# pwm_outputs.net
KiCad netlist of a schematic drawn in Altium Designer
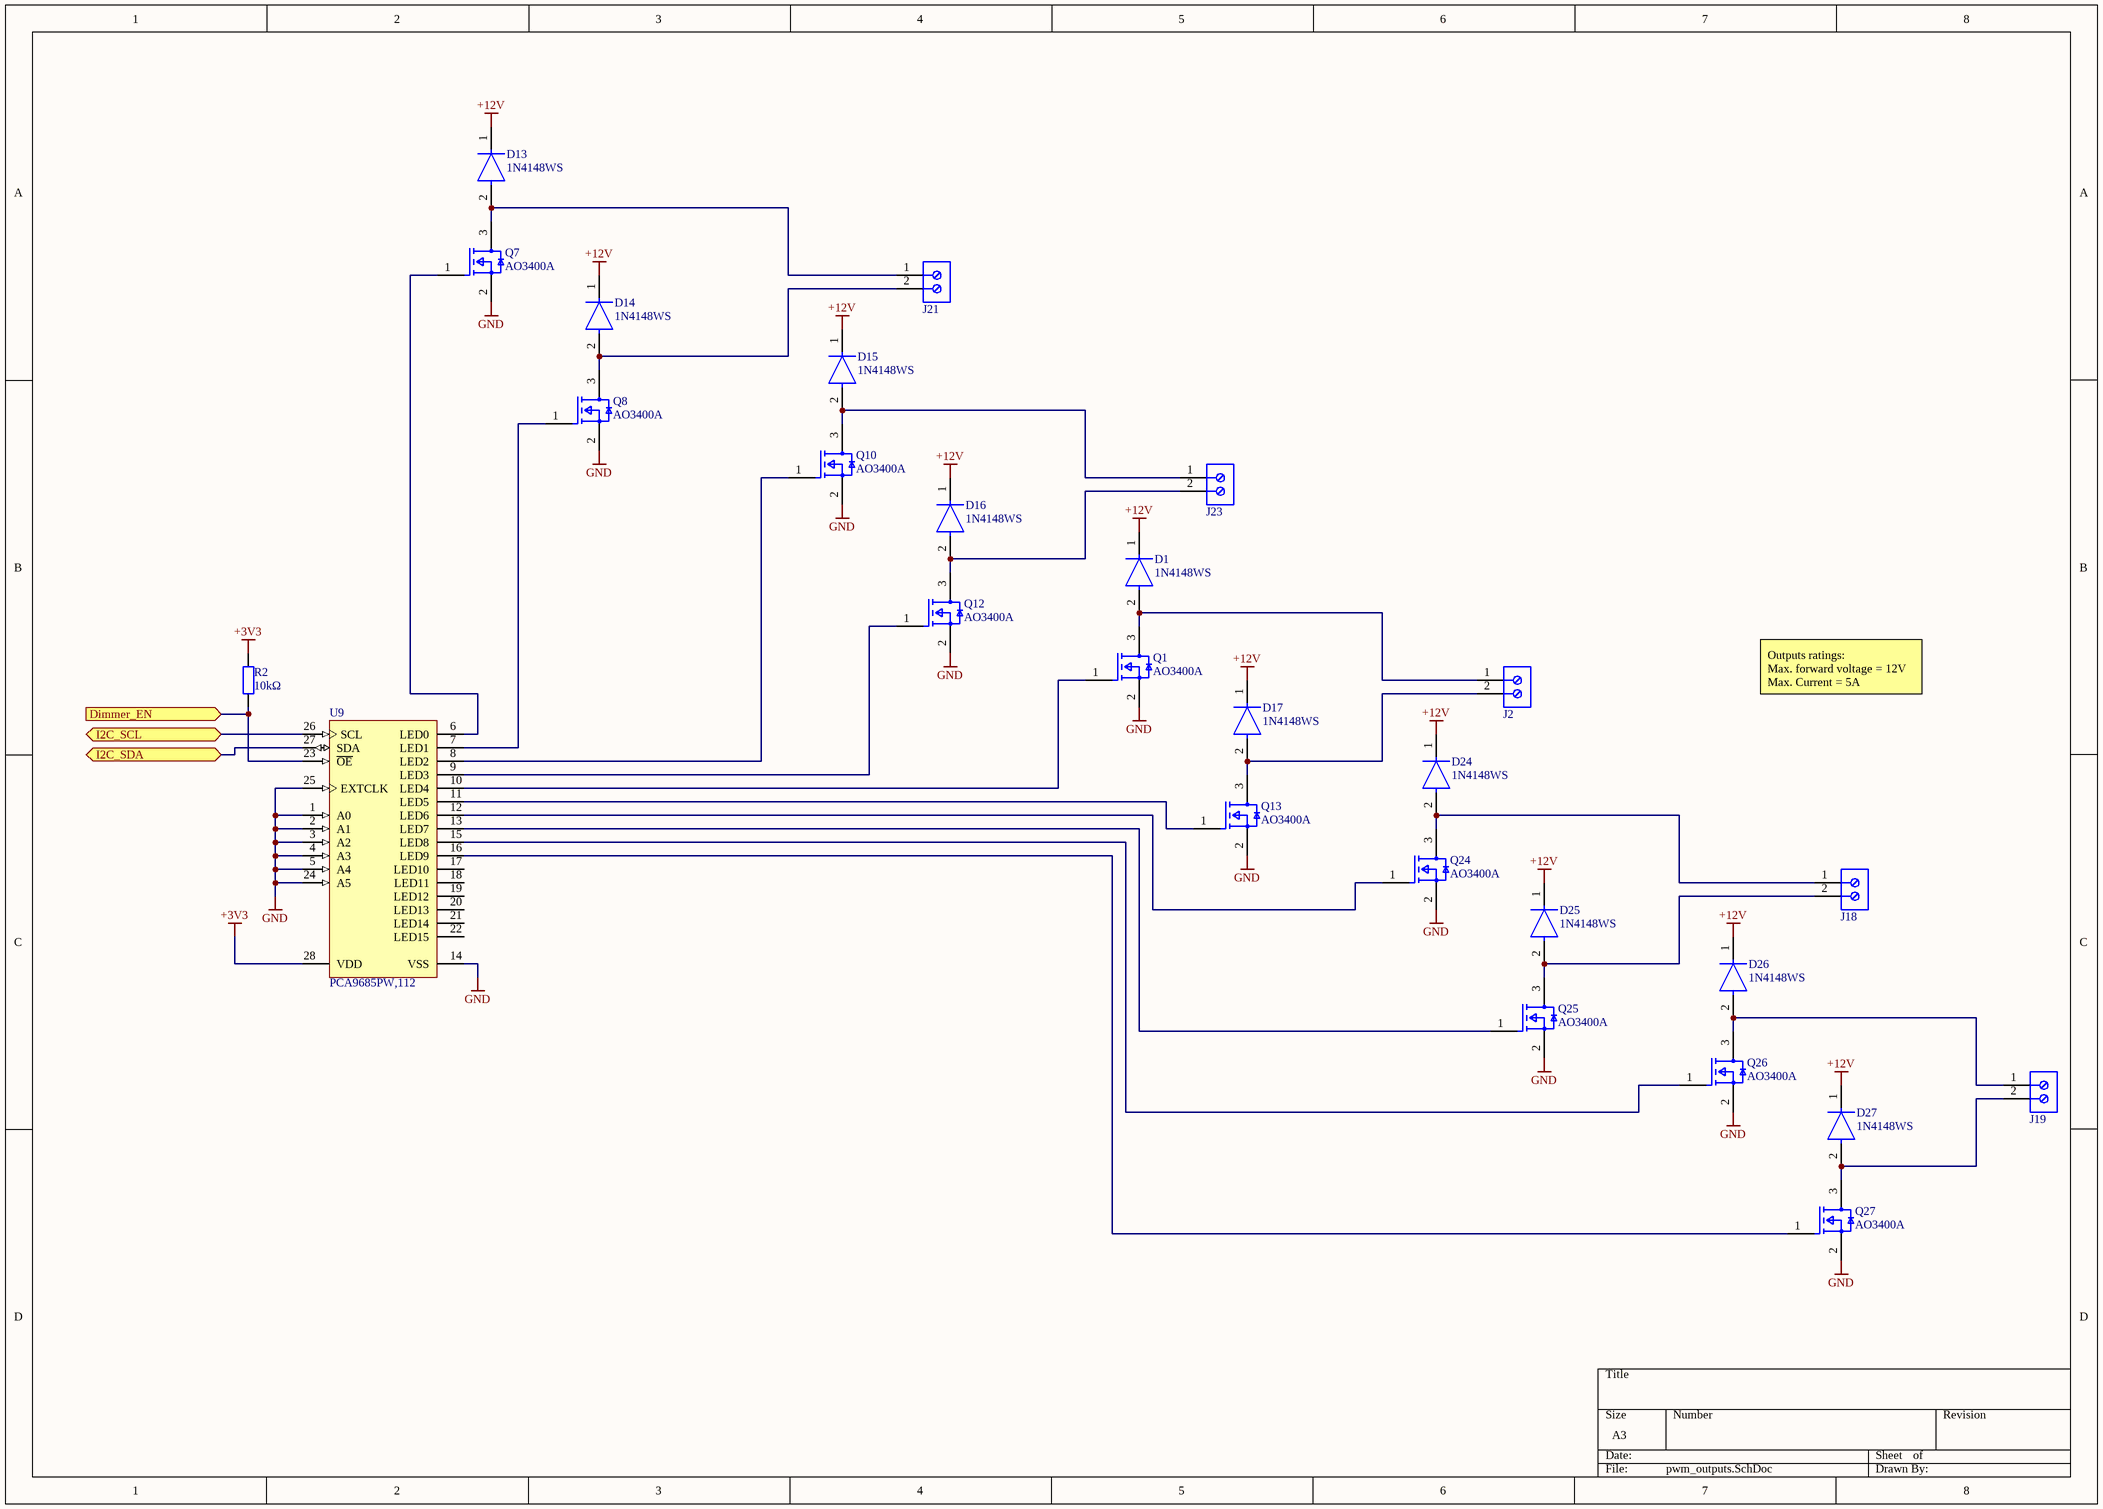
[diagram p0: pwm_outputs.SchDoc]

(export (version "E")
  (design (tool "Eeschema 10.0.6"))
  (components
    (comp (ref "D1")
      (value "1N4148WS")
      (footprint "FP-477AB-IPC_C")
      (description "DIODE GEN PURP 75V 150MA SOD323F")
      (libsource (lib "Altium Content Vault") (part "d7152d700b627762746794eb795d46e"))
    )
    (comp (ref "D13")
      (value "1N4148WS")
      (footprint "FP-477AB-IPC_C")
      (description "DIODE GEN PURP 75V 150MA SOD323F")
      (libsource (lib "Altium Content Vault") (part "d7152d700b627762746794eb795d46e"))
    )
    (comp (ref "D14")
      (value "1N4148WS")
      (footprint "FP-477AB-IPC_C")
      (description "DIODE GEN PURP 75V 150MA SOD323F")
      (libsource (lib "Altium Content Vault") (part "d7152d700b627762746794eb795d46e"))
    )
    (comp (ref "D15")
      (value "1N4148WS")
      (footprint "FP-477AB-IPC_C")
      (description "DIODE GEN PURP 75V 150MA SOD323F")
      (libsource (lib "Altium Content Vault") (part "d7152d700b627762746794eb795d46e"))
    )
    (comp (ref "D16")
      (value "1N4148WS")
      (footprint "FP-477AB-IPC_C")
      (description "DIODE GEN PURP 75V 150MA SOD323F")
      (libsource (lib "Altium Content Vault") (part "d7152d700b627762746794eb795d46e"))
    )
    (comp (ref "D17")
      (value "1N4148WS")
      (footprint "FP-477AB-IPC_C")
      (description "DIODE GEN PURP 75V 150MA SOD323F")
      (libsource (lib "Altium Content Vault") (part "d7152d700b627762746794eb795d46e"))
    )
    (comp (ref "D24")
      (value "1N4148WS")
      (footprint "FP-477AB-IPC_C")
      (description "DIODE GEN PURP 75V 150MA SOD323F")
      (libsource (lib "Altium Content Vault") (part "d7152d700b627762746794eb795d46e"))
    )
    (comp (ref "D25")
      (value "1N4148WS")
      (footprint "FP-477AB-IPC_C")
      (description "DIODE GEN PURP 75V 150MA SOD323F")
      (libsource (lib "Altium Content Vault") (part "d7152d700b627762746794eb795d46e"))
    )
    (comp (ref "D26")
      (value "1N4148WS")
      (footprint "FP-477AB-IPC_C")
      (description "DIODE GEN PURP 75V 150MA SOD323F")
      (libsource (lib "Altium Content Vault") (part "d7152d700b627762746794eb795d46e"))
    )
    (comp (ref "D27")
      (value "1N4148WS")
      (footprint "FP-477AB-IPC_C")
      (description "DIODE GEN PURP 75V 150MA SOD323F")
      (libsource (lib "Altium Content Vault") (part "d7152d700b627762746794eb795d46e"))
    )
    (comp (ref "J2")
      (value "282836-2")
      (footprint "TECO-282836-2_V")
      (description "Female Header, Pitch 5 mm, 1 x 2 Position, Height 10 mm, Tail Length 3.5 mm, Rohs, Bulk")
      (fields (field (name "VOLTAGE") "300V") (field (name "MANUFACTURER") "TE Connectivity"))
      (libsource (lib "Altium Content Vault") (part "CN-1P-F-TB2"))
    )
    (comp (ref "J18")
      (value "282836-2")
      (footprint "TECO-282836-2_V")
      (description "Female Header, Pitch 5 mm, 1 x 2 Position, Height 10 mm, Tail Length 3.5 mm, Rohs, Bulk")
      (fields (field (name "VOLTAGE") "300V") (field (name "MANUFACTURER") "TE Connectivity"))
      (libsource (lib "Altium Content Vault") (part "CN-1P-F-TB2"))
    )
    (comp (ref "J19")
      (value "282836-2")
      (footprint "TECO-282836-2_V")
      (description "Female Header, Pitch 5 mm, 1 x 2 Position, Height 10 mm, Tail Length 3.5 mm, Rohs, Bulk")
      (fields (field (name "VOLTAGE") "300V") (field (name "MANUFACTURER") "TE Connectivity"))
      (libsource (lib "Altium Content Vault") (part "CN-1P-F-TB2"))
    )
    (comp (ref "J21")
      (value "282836-2")
      (footprint "TECO-282836-2_V")
      (description "Female Header, Pitch 5 mm, 1 x 2 Position, Height 10 mm, Tail Length 3.5 mm, Rohs, Bulk")
      (fields (field (name "VOLTAGE") "300V") (field (name "MANUFACTURER") "TE Connectivity"))
      (libsource (lib "Altium Content Vault") (part "CN-1P-F-TB2"))
    )
    (comp (ref "J23")
      (value "282836-2")
      (footprint "TECO-282836-2_V")
      (description "Female Header, Pitch 5 mm, 1 x 2 Position, Height 10 mm, Tail Length 3.5 mm, Rohs, Bulk")
      (fields (field (name "VOLTAGE") "300V") (field (name "MANUFACTURER") "TE Connectivity"))
      (libsource (lib "Altium Content Vault") (part "CN-1P-F-TB2"))
    )
    (comp (ref "Q1")
      (value "AO3400A")
      (footprint "SOT-23")
      (description "MOSFET N-CH 30V 5.7A SOT23")
      (libsource (lib "integrated_library") (part "MOSFET_AO3400A"))
    )
    (comp (ref "Q7")
      (value "AO3400A")
      (footprint "SOT-23")
      (description "MOSFET N-CH 30V 5.7A SOT23")
      (libsource (lib "integrated_library") (part "MOSFET_AO3400A"))
    )
    (comp (ref "Q8")
      (value "AO3400A")
      (footprint "SOT-23")
      (description "MOSFET N-CH 30V 5.7A SOT23")
      (libsource (lib "integrated_library") (part "MOSFET_AO3400A"))
    )
    (comp (ref "Q10")
      (value "AO3400A")
      (footprint "SOT-23")
      (description "MOSFET N-CH 30V 5.7A SOT23")
      (libsource (lib "integrated_library") (part "MOSFET_AO3400A"))
    )
    (comp (ref "Q12")
      (value "AO3400A")
      (footprint "SOT-23")
      (description "MOSFET N-CH 30V 5.7A SOT23")
      (libsource (lib "integrated_library") (part "MOSFET_AO3400A"))
    )
    (comp (ref "Q13")
      (value "AO3400A")
      (footprint "SOT-23")
      (description "MOSFET N-CH 30V 5.7A SOT23")
      (libsource (lib "integrated_library") (part "MOSFET_AO3400A"))
    )
    (comp (ref "Q24")
      (value "AO3400A")
      (footprint "SOT-23")
      (description "MOSFET N-CH 30V 5.7A SOT23")
      (libsource (lib "integrated_library") (part "MOSFET_AO3400A"))
    )
    (comp (ref "Q25")
      (value "AO3400A")
      (footprint "SOT-23")
      (description "MOSFET N-CH 30V 5.7A SOT23")
      (libsource (lib "integrated_library") (part "MOSFET_AO3400A"))
    )
    (comp (ref "Q26")
      (value "AO3400A")
      (footprint "SOT-23")
      (description "MOSFET N-CH 30V 5.7A SOT23")
      (libsource (lib "integrated_library") (part "MOSFET_AO3400A"))
    )
    (comp (ref "Q27")
      (value "AO3400A")
      (footprint "SOT-23")
      (description "MOSFET N-CH 30V 5.7A SOT23")
      (libsource (lib "integrated_library") (part "MOSFET_AO3400A"))
    )
    (comp (ref "R2")
      (value "10kΩ")
      (footprint "RESC2013X50X30ML20T20")
      (description "Resistor")
      (libsource (lib "PCB_Project") (part "Res_0805"))
    )
    (comp (ref "U9")
      (value "PCA9685PW,112")
      (footprint "SOT361-1_V")
      (fields (field (name "PARTNUMBER") "PCA9685"))
      (libsource (lib "Altium Content Vault") (part "NXP-PCA9685-SOT361-1"))
    )
  )
  (nets
    (net (code "1") (name "+3V3") (class "Default")
      (node (ref "R2") (pin "2") (pinfunction "2_2") (pintype "passive"))
      (node (ref "U9") (pin "28") (pinfunction "VDD_28") (pintype "power_in"))
    )
    (net (code "2") (name "+12V") (class "Default")
      (node (ref "D1") (pin "1") (pinfunction "C_1") (pintype "passive"))
      (node (ref "D13") (pin "1") (pinfunction "C_1") (pintype "passive"))
      (node (ref "D14") (pin "1") (pinfunction "C_1") (pintype "passive"))
      (node (ref "D15") (pin "1") (pinfunction "C_1") (pintype "passive"))
      (node (ref "D16") (pin "1") (pinfunction "C_1") (pintype "passive"))
      (node (ref "D17") (pin "1") (pinfunction "C_1") (pintype "passive"))
      (node (ref "D24") (pin "1") (pinfunction "C_1") (pintype "passive"))
      (node (ref "D25") (pin "1") (pinfunction "C_1") (pintype "passive"))
      (node (ref "D26") (pin "1") (pinfunction "C_1") (pintype "passive"))
      (node (ref "D27") (pin "1") (pinfunction "C_1") (pintype "passive"))
    )
    (net (code "3") (name "/Dimmer_EN") (class "Default")
      (node (ref "R2") (pin "1") (pinfunction "1_1") (pintype "passive"))
      (node (ref "U9") (pin "23") (pinfunction "~{OE}_23") (pintype "input"))
    )
    (net (code "4") (name "/I2C_SCL") (class "Default")
      (node (ref "U9") (pin "26") (pinfunction "SCL_26") (pintype "input"))
    )
    (net (code "5") (name "/I2C_SDA") (class "Default")
      (node (ref "U9") (pin "27") (pinfunction "SDA_27") (pintype "bidirectional"))
    )
    (net (code "6") (name "GND") (class "Default")
      (node (ref "Q1") (pin "2") (pinfunction "S_2") (pintype "passive"))
      (node (ref "Q10") (pin "2") (pinfunction "S_2") (pintype "passive"))
      (node (ref "Q12") (pin "2") (pinfunction "S_2") (pintype "passive"))
      (node (ref "Q13") (pin "2") (pinfunction "S_2") (pintype "passive"))
      (node (ref "Q24") (pin "2") (pinfunction "S_2") (pintype "passive"))
      (node (ref "Q25") (pin "2") (pinfunction "S_2") (pintype "passive"))
      (node (ref "Q26") (pin "2") (pinfunction "S_2") (pintype "passive"))
      (node (ref "Q27") (pin "2") (pinfunction "S_2") (pintype "passive"))
      (node (ref "Q7") (pin "2") (pinfunction "S_2") (pintype "passive"))
      (node (ref "Q8") (pin "2") (pinfunction "S_2") (pintype "passive"))
      (node (ref "U9") (pin "1") (pinfunction "A0_1") (pintype "input"))
      (node (ref "U9") (pin "14") (pinfunction "VSS_14") (pintype "power_in"))
      (node (ref "U9") (pin "2") (pinfunction "A1_2") (pintype "input"))
      (node (ref "U9") (pin "24") (pinfunction "A5_24") (pintype "input"))
      (node (ref "U9") (pin "25") (pinfunction "EXTCLK_25") (pintype "input"))
      (node (ref "U9") (pin "3") (pinfunction "A2_3") (pintype "input"))
      (node (ref "U9") (pin "4") (pinfunction "A3_4") (pintype "input"))
      (node (ref "U9") (pin "5") (pinfunction "A4_5") (pintype "input"))
    )
    (net (code "7") (name "Net-(D1-A)") (class "Default")
      (node (ref "D1") (pin "2") (pinfunction "A_2") (pintype "passive"))
      (node (ref "J2") (pin "1") (pinfunction "1_1") (pintype "passive"))
      (node (ref "Q1") (pin "3") (pinfunction "D_3") (pintype "passive"))
    )
    (net (code "8") (name "Net-(D13-A)") (class "Default")
      (node (ref "D13") (pin "2") (pinfunction "A_2") (pintype "passive"))
      (node (ref "J21") (pin "1") (pinfunction "1_1") (pintype "passive"))
      (node (ref "Q7") (pin "3") (pinfunction "D_3") (pintype "passive"))
    )
    (net (code "9") (name "Net-(D14-A)") (class "Default")
      (node (ref "D14") (pin "2") (pinfunction "A_2") (pintype "passive"))
      (node (ref "J21") (pin "2") (pinfunction "2_2") (pintype "passive"))
      (node (ref "Q8") (pin "3") (pinfunction "D_3") (pintype "passive"))
    )
    (net (code "10") (name "Net-(D15-A)") (class "Default")
      (node (ref "D15") (pin "2") (pinfunction "A_2") (pintype "passive"))
      (node (ref "J23") (pin "1") (pinfunction "1_1") (pintype "passive"))
      (node (ref "Q10") (pin "3") (pinfunction "D_3") (pintype "passive"))
    )
    (net (code "11") (name "Net-(D16-A)") (class "Default")
      (node (ref "D16") (pin "2") (pinfunction "A_2") (pintype "passive"))
      (node (ref "J23") (pin "2") (pinfunction "2_2") (pintype "passive"))
      (node (ref "Q12") (pin "3") (pinfunction "D_3") (pintype "passive"))
    )
    (net (code "12") (name "Net-(D17-A)") (class "Default")
      (node (ref "D17") (pin "2") (pinfunction "A_2") (pintype "passive"))
      (node (ref "J2") (pin "2") (pinfunction "2_2") (pintype "passive"))
      (node (ref "Q13") (pin "3") (pinfunction "D_3") (pintype "passive"))
    )
    (net (code "13") (name "Net-(D24-A)") (class "Default")
      (node (ref "D24") (pin "2") (pinfunction "A_2") (pintype "passive"))
      (node (ref "J18") (pin "1") (pinfunction "1_1") (pintype "passive"))
      (node (ref "Q24") (pin "3") (pinfunction "D_3") (pintype "passive"))
    )
    (net (code "14") (name "Net-(D25-A)") (class "Default")
      (node (ref "D25") (pin "2") (pinfunction "A_2") (pintype "passive"))
      (node (ref "J18") (pin "2") (pinfunction "2_2") (pintype "passive"))
      (node (ref "Q25") (pin "3") (pinfunction "D_3") (pintype "passive"))
    )
    (net (code "15") (name "Net-(D26-A)") (class "Default")
      (node (ref "D26") (pin "2") (pinfunction "A_2") (pintype "passive"))
      (node (ref "J19") (pin "1") (pinfunction "1_1") (pintype "passive"))
      (node (ref "Q26") (pin "3") (pinfunction "D_3") (pintype "passive"))
    )
    (net (code "16") (name "Net-(D27-A)") (class "Default")
      (node (ref "D27") (pin "2") (pinfunction "A_2") (pintype "passive"))
      (node (ref "J19") (pin "2") (pinfunction "2_2") (pintype "passive"))
      (node (ref "Q27") (pin "3") (pinfunction "D_3") (pintype "passive"))
    )
    (net (code "17") (name "Net-(Q1-G)") (class "Default")
      (node (ref "Q1") (pin "1") (pinfunction "G_1") (pintype "passive"))
      (node (ref "U9") (pin "10") (pinfunction "LED4_10") (pintype "tri_state"))
    )
    (net (code "18") (name "Net-(Q7-G)") (class "Default")
      (node (ref "Q7") (pin "1") (pinfunction "G_1") (pintype "passive"))
      (node (ref "U9") (pin "6") (pinfunction "LED0_6") (pintype "tri_state"))
    )
    (net (code "19") (name "Net-(Q8-G)") (class "Default")
      (node (ref "Q8") (pin "1") (pinfunction "G_1") (pintype "passive"))
      (node (ref "U9") (pin "7") (pinfunction "LED1_7") (pintype "tri_state"))
    )
    (net (code "20") (name "Net-(Q10-G)") (class "Default")
      (node (ref "Q10") (pin "1") (pinfunction "G_1") (pintype "passive"))
      (node (ref "U9") (pin "8") (pinfunction "LED2_8") (pintype "tri_state"))
    )
    (net (code "21") (name "Net-(Q12-G)") (class "Default")
      (node (ref "Q12") (pin "1") (pinfunction "G_1") (pintype "passive"))
      (node (ref "U9") (pin "9") (pinfunction "LED3_9") (pintype "tri_state"))
    )
    (net (code "22") (name "Net-(Q13-G)") (class "Default")
      (node (ref "Q13") (pin "1") (pinfunction "G_1") (pintype "passive"))
      (node (ref "U9") (pin "11") (pinfunction "LED5_11") (pintype "tri_state"))
    )
    (net (code "23") (name "Net-(Q24-G)") (class "Default")
      (node (ref "Q24") (pin "1") (pinfunction "G_1") (pintype "passive"))
      (node (ref "U9") (pin "12") (pinfunction "LED6_12") (pintype "tri_state"))
    )
    (net (code "24") (name "Net-(Q25-G)") (class "Default")
      (node (ref "Q25") (pin "1") (pinfunction "G_1") (pintype "passive"))
      (node (ref "U9") (pin "13") (pinfunction "LED7_13") (pintype "tri_state"))
    )
    (net (code "25") (name "Net-(Q26-G)") (class "Default")
      (node (ref "Q26") (pin "1") (pinfunction "G_1") (pintype "passive"))
      (node (ref "U9") (pin "15") (pinfunction "LED8_15") (pintype "tri_state"))
    )
    (net (code "26") (name "Net-(Q27-G)") (class "Default")
      (node (ref "Q27") (pin "1") (pinfunction "G_1") (pintype "passive"))
      (node (ref "U9") (pin "16") (pinfunction "LED9_16") (pintype "tri_state"))
    )
    (net (code "27") (name "unconnected-(U9-LED10-Pad17)") (class "Default")
      (node (ref "U9") (pin "17") (pinfunction "LED10_17") (pintype "tri_state"))
    )
    (net (code "28") (name "unconnected-(U9-LED11-Pad18)") (class "Default")
      (node (ref "U9") (pin "18") (pinfunction "LED11_18") (pintype "tri_state"))
    )
    (net (code "29") (name "unconnected-(U9-LED12-Pad19)") (class "Default")
      (node (ref "U9") (pin "19") (pinfunction "LED12_19") (pintype "tri_state"))
    )
    (net (code "30") (name "unconnected-(U9-LED13-Pad20)") (class "Default")
      (node (ref "U9") (pin "20") (pinfunction "LED13_20") (pintype "tri_state"))
    )
    (net (code "31") (name "unconnected-(U9-LED14-Pad21)") (class "Default")
      (node (ref "U9") (pin "21") (pinfunction "LED14_21") (pintype "tri_state"))
    )
    (net (code "32") (name "unconnected-(U9-LED15-Pad22)") (class "Default")
      (node (ref "U9") (pin "22") (pinfunction "LED15_22") (pintype "tri_state"))
    )
  )
)
